# AUPSC.net
KiCad netlist of a schematic drawn in Altium Designer
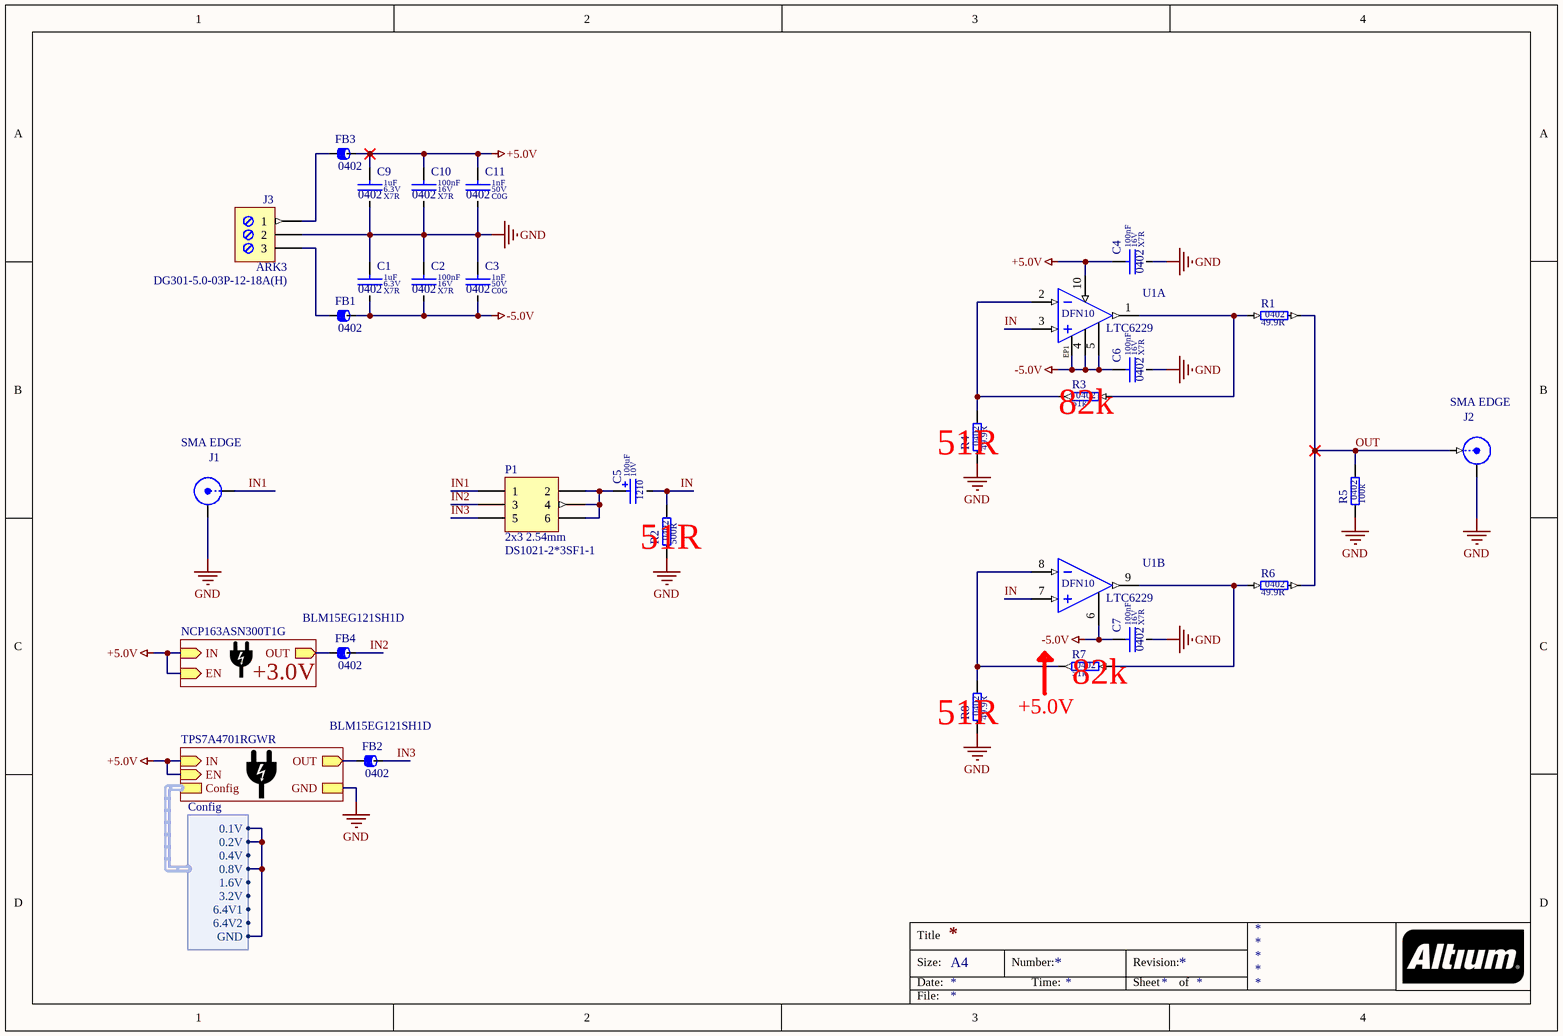
[diagram p0: AUPSC.SchDoc]

(export (version "E")
  (design (tool "Eeschema 10.0.6"))
  (components
    (comp (ref "C1")
      (value "1uF")
      (footprint "C_0402_1005")
      (description "Capacitor")
      (fields
        (field (name "DIELECTRIC") "X7R")
        (field (name "VOLTAGE") "6.3V")
        (field (name "SCH_FOOTPRINT") "0402")
        (field (name "PART NUMBER") "C_1uF_6.3V_X7R_0402_10")
        (field (name "MANUFACTURER") "Murata")
      )
      (libsource (lib "Library") (part "C"))
    )
    (comp (ref "C2")
      (value "100nF")
      (footprint "C_0402_1005")
      (description "Capacitor")
      (fields
        (field (name "DIELECTRIC") "X7R")
        (field (name "VOLTAGE") "16V")
        (field (name "SCH_FOOTPRINT") "0402")
        (field (name "PART NUMBER") "C_100nF_16V_X7R_0402_10")
        (field (name "MANUFACTURER") "Murata")
      )
      (libsource (lib "Library") (part "C"))
    )
    (comp (ref "C3")
      (value "1nF")
      (footprint "C_0402_1005")
      (description "Capacitor")
      (fields
        (field (name "DIELECTRIC") "C0G")
        (field (name "VOLTAGE") "50V")
        (field (name "SCH_FOOTPRINT") "0402")
        (field (name "PART NUMBER") "C_1nF_50V_C0G_0402_5")
        (field (name "MANUFACTURER") "Murata")
      )
      (libsource (lib "Library") (part "C"))
    )
    (comp (ref "C4")
      (value "100nF")
      (footprint "C_0402_1005")
      (description "Capacitor")
      (fields
        (field (name "DIELECTRIC") "X7R")
        (field (name "VOLTAGE") "16V")
        (field (name "SCH_FOOTPRINT") "0402")
        (field (name "PART NUMBER") "C_100nF_16V_X7R_0402_10")
        (field (name "MANUFACTURER") "Murata")
      )
      (libsource (lib "Library") (part "C"))
    )
    (comp (ref "C5")
      (value "100uF")
      (footprint "CT_1210_3225")
      (description "Capacitor")
      (fields
        (field (name "SCH_FOOTPRINT") "1210")
        (field (name "VOLTAGE") "10V")
        (field (name "PART NUMBER") "CT_100uF_10V_TA2O5_1210_20")
        (field (name "MANUFACTURER") "AVX")
      )
      (libsource (lib "Library") (part "CT"))
    )
    (comp (ref "C6")
      (value "100nF")
      (footprint "C_0402_1005")
      (description "Capacitor")
      (fields
        (field (name "DIELECTRIC") "X7R")
        (field (name "VOLTAGE") "16V")
        (field (name "SCH_FOOTPRINT") "0402")
        (field (name "PART NUMBER") "C_100nF_16V_X7R_0402_10")
        (field (name "MANUFACTURER") "Murata")
      )
      (libsource (lib "Library") (part "C"))
    )
    (comp (ref "C7")
      (value "100nF")
      (footprint "C_0402_1005")
      (description "Capacitor")
      (fields
        (field (name "DIELECTRIC") "X7R")
        (field (name "VOLTAGE") "16V")
        (field (name "SCH_FOOTPRINT") "0402")
        (field (name "PART NUMBER") "C_100nF_16V_X7R_0402_10")
        (field (name "MANUFACTURER") "Murata")
      )
      (libsource (lib "Library") (part "C"))
    )
    (comp (ref "C9")
      (value "1uF")
      (footprint "C_0402_1005")
      (description "Capacitor")
      (fields
        (field (name "DIELECTRIC") "X7R")
        (field (name "VOLTAGE") "6.3V")
        (field (name "SCH_FOOTPRINT") "0402")
        (field (name "PART NUMBER") "C_1uF_6.3V_X7R_0402_10")
        (field (name "MANUFACTURER") "Murata")
      )
      (libsource (lib "Library") (part "C"))
    )
    (comp (ref "C10")
      (value "100nF")
      (footprint "C_0402_1005")
      (description "Capacitor")
      (fields
        (field (name "DIELECTRIC") "X7R")
        (field (name "VOLTAGE") "16V")
        (field (name "SCH_FOOTPRINT") "0402")
        (field (name "PART NUMBER") "C_100nF_16V_X7R_0402_10")
        (field (name "MANUFACTURER") "Murata")
      )
      (libsource (lib "Library") (part "C"))
    )
    (comp (ref "C11")
      (value "1nF")
      (footprint "C_0402_1005")
      (description "Capacitor")
      (fields
        (field (name "DIELECTRIC") "C0G")
        (field (name "VOLTAGE") "50V")
        (field (name "SCH_FOOTPRINT") "0402")
        (field (name "PART NUMBER") "C_1nF_50V_C0G_0402_5")
        (field (name "MANUFACTURER") "Murata")
      )
      (libsource (lib "Library") (part "C"))
    )
    (comp (ref "FB1")
      (value "Ferrite bead")
      (footprint "FB_0402_1005")
      (description "Ferrite Bead")
      (fields
        (field (name "PART NUMBER") "FB_BLM15EG121SH1D")
        (field (name "SCH_FOOTPRINT") "0402")
        (field (name "MANUFACTURER") "Murata")
      )
      (libsource (lib "Library") (part "FB"))
    )
    (comp (ref "FB2")
      (value "BLM15EG121SH1D")
      (footprint "FB_0402_1005")
      (description "Ferrite Bead")
      (fields
        (field (name "PART NUMBER") "FB_BLM15EG121SH1D")
        (field (name "SCH_FOOTPRINT") "0402")
        (field (name "MANUFACTURER") "Murata")
      )
      (libsource (lib "Library") (part "FB"))
    )
    (comp (ref "FB3")
      (value "Ferrite bead")
      (footprint "FB_0402_1005")
      (description "Ferrite Bead")
      (fields
        (field (name "PART NUMBER") "FB_BLM15EG121SH1D")
        (field (name "SCH_FOOTPRINT") "0402")
        (field (name "MANUFACTURER") "Murata")
      )
      (libsource (lib "") (part "FB_1"))
    )
    (comp (ref "FB4")
      (value "BLM15EG121SH1D")
      (footprint "FB_0402_1005")
      (description "Ferrite Bead")
      (fields
        (field (name "PART NUMBER") "FB_BLM15EG121SH1D")
        (field (name "SCH_FOOTPRINT") "0402")
        (field (name "MANUFACTURER") "Murata")
      )
      (libsource (lib "Library") (part "FB"))
    )
    (comp (ref "J1")
      (value "SMA EDGE")
      (footprint "J_SMA_EDGE")
      (description "SMA connector")
      (fields (field (name "PART NUMBER") "J_SMA_EDGE_UNIVERSAL") (field (name "SCH_FOOTPRINT") "SMA EDGE"))
      (libsource (lib "Library") (part "J_SMA"))
    )
    (comp (ref "J2")
      (value "SMA EDGE")
      (footprint "J_SMA_EDGE")
      (description "SMA connector")
      (fields (field (name "PART NUMBER") "J_SMA_EDGE_UNIVERSAL") (field (name "SCH_FOOTPRINT") "SMA EDGE"))
      (libsource (lib "") (part "J_SMA_1"))
    )
    (comp (ref "J3")
      (value "DG301-5.0-03P-12-18A(H)")
      (footprint "J_ARK3")
      (description "ARK Screw terminal, 3-Pin")
      (fields
        (field (name "SCH_FOOTPRINT") "ARK3")
        (field (name "PART NUMBER") "J_TB-5.0-P-3P")
        (field (name "MANUFACTURER") "DEGSON ELECTRONICS")
      )
      (libsource (lib "Library") (part "J_ARK3"))
    )
    (comp (ref "P1")
      (value "DS1021-2*3SF1-1")
      (footprint "P_HEADER_2x3_2.54")
      (description "Pin Header")
      (fields
        (field (name "SCH_FOOTPRINT") "2x3 2.54mm")
        (field (name "PART NUMBER") "P_HEADER_2x3_2.54")
        (field (name "MANUFACTURER") "Connfly")
      )
      (libsource (lib "Library") (part "P_HEADER_2x3"))
    )
    (comp (ref "R1")
      (value "49.9R")
      (footprint "R_0402_1005")
      (fields
        (field (name "SCH_FOOTPRINT") "0402")
        (field (name "PART NUMBER") "R_49.9R_0402_1")
        (field (name "VOLTAGE") "50V")
        (field (name "POWER") "100mW")
      )
      (libsource (lib "") (part "R_2"))
    )
    (comp (ref "R2")
      (value "500R")
      (footprint "R_0402_1005")
      (fields
        (field (name "SCH_FOOTPRINT") "0402")
        (field (name "PART NUMBER") "R_500R_0402_0.1")
        (field (name "VOLTAGE") "75V")
        (field (name "POWER") "50mW")
      )
      (libsource (lib "Library") (part "R"))
    )
    (comp (ref "R3")
      (value "51k")
      (footprint "R_0402_1005")
      (fields
        (field (name "SCH_FOOTPRINT") "0402")
        (field (name "PART NUMBER") "R_51k_0402_1")
        (field (name "VOLTAGE") "50V")
        (field (name "POWER") "62.5mW")
      )
      (libsource (lib "") (part "R_1"))
    )
    (comp (ref "R4")
      (value "49.9R")
      (footprint "R_0402_1005")
      (fields
        (field (name "SCH_FOOTPRINT") "0402")
        (field (name "PART NUMBER") "R_49.9R_0402_1")
        (field (name "VOLTAGE") "50V")
        (field (name "POWER") "100mW")
      )
      (libsource (lib "Library") (part "R"))
    )
    (comp (ref "R5")
      (value "100k")
      (footprint "R_0402_1005")
      (fields
        (field (name "SCH_FOOTPRINT") "0402")
        (field (name "PART NUMBER") "R_100k_0402_1")
        (field (name "VOLTAGE") "50V")
        (field (name "POWER") "63mW")
      )
      (libsource (lib "Library") (part "R"))
    )
    (comp (ref "R6")
      (value "49.9R")
      (footprint "R_0402_1005")
      (fields
        (field (name "SCH_FOOTPRINT") "0402")
        (field (name "PART NUMBER") "R_49.9R_0402_1")
        (field (name "VOLTAGE") "50V")
        (field (name "POWER") "100mW")
      )
      (libsource (lib "") (part "R_2"))
    )
    (comp (ref "R7")
      (value "51k")
      (footprint "R_0402_1005")
      (fields
        (field (name "SCH_FOOTPRINT") "0402")
        (field (name "PART NUMBER") "R_51k_0402_1")
        (field (name "VOLTAGE") "50V")
        (field (name "POWER") "62.5mW")
      )
      (libsource (lib "") (part "R_1"))
    )
    (comp (ref "R8")
      (value "49.9R")
      (footprint "R_0402_1005")
      (fields
        (field (name "SCH_FOOTPRINT") "0402")
        (field (name "PART NUMBER") "R_49.9R_0402_1")
        (field (name "VOLTAGE") "50V")
        (field (name "POWER") "100mW")
      )
      (libsource (lib "Library") (part "R"))
    )
    (comp (ref "U1")
      (value "LTC6229")
      (footprint "DFN10_3x3_EP")
      (fields
        (field (name "SCH_FOOTPRINT") "DFN10")
        (field (name "PART NUMBER") "U_ADA4807-2ACPZ-R2")
        (field (name "MANUFACTURER") "Analog Devices")
        (field (name "MANUFACTURER PART NUMBER") "ADA4807-2ACPZ-R2")
      )
      (libsource (lib "Library") (part "A_10PIN_TYPICAL"))
    )
  )
  (nets
    (net (code "2") (name "+5.0V") (class "Default")
      (node (ref "C10") (pin "1") (pinfunction "1_1") (pintype "passive"))
      (node (ref "C11") (pin "1") (pinfunction "1_1") (pintype "passive"))
      (node (ref "C4") (pin "1") (pinfunction "1_1") (pintype "passive"))
      (node (ref "C9") (pin "1") (pinfunction "1_1") (pintype "passive"))
      (node (ref "FB3") (pin "2") (pintype "output"))
      (node (ref "U1") (pin "10") (pinfunction "VDD_10") (pintype "input"))
    )
    (net (code "3") (name "-5.0V") (class "Default")
      (node (ref "C1") (pin "2") (pinfunction "2_2") (pintype "passive"))
      (node (ref "C2") (pin "2") (pinfunction "2_2") (pintype "passive"))
      (node (ref "C3") (pin "2") (pinfunction "2_2") (pintype "passive"))
      (node (ref "C6") (pin "1") (pinfunction "1_1") (pintype "passive"))
      (node (ref "C7") (pin "1") (pinfunction "1_1") (pintype "passive"))
      (node (ref "FB1") (pin "2") (pintype "passive"))
      (node (ref "U1") (pin "4") (pinfunction "GND_4") (pintype "power_in"))
      (node (ref "U1") (pin "5") (pinfunction "~{SHNDA}_5") (pintype "power_in"))
      (node (ref "U1") (pin "6") (pinfunction "~{SHNDB}_6") (pintype "power_in"))
      (node (ref "U1") (pin "EP1") (pinfunction "GND_EP1") (pintype "power_in"))
    )
    (net (code "4") (name "/IN") (class "Default")
      (node (ref "C5") (pin "2") (pinfunction "2_2") (pintype "passive"))
      (node (ref "R2") (pin "2") (pinfunction "2_2") (pintype "passive"))
      (node (ref "U1") (pin "3") (pinfunction "IN+_3") (pintype "input"))
      (node (ref "U1") (pin "7") (pinfunction "IN+_7") (pintype "input"))
    )
    (net (code "5") (name "/IN1") (class "Default")
      (node (ref "J1") (pin "1") (pinfunction "X_1") (pintype "passive"))
      (node (ref "P1") (pin "1") (pinfunction "1_1") (pintype "passive"))
    )
    (net (code "6") (name "/IN2") (class "Default")
      (node (ref "FB4") (pin "2") (pintype "passive"))
      (node (ref "P1") (pin "3") (pinfunction "3_3") (pintype "passive"))
    )
    (net (code "7") (name "/IN3") (class "Default")
      (node (ref "FB2") (pin "2") (pintype "passive"))
      (node (ref "P1") (pin "5") (pinfunction "5_5") (pintype "passive"))
    )
    (net (code "8") (name "/OUT") (class "Default")
      (node (ref "J2") (pin "1") (pinfunction "X_1") (pintype "input"))
      (node (ref "R1") (pin "2") (pinfunction "2_2") (pintype "output"))
      (node (ref "R5") (pin "2") (pinfunction "2_2") (pintype "passive"))
      (node (ref "R6") (pin "2") (pinfunction "2_2") (pintype "output"))
    )
    (net (code "9") (name "/OUT_1") (class "Default") (node (ref "FB2") (pin "1") (pintype "passive")))
    (net (code "10") (name "/OUT_2") (class "Default") (node (ref "FB4") (pin "1") (pintype "passive")))
    (net (code "12") (name "GND") (class "Default")
      (node (ref "C1") (pin "1") (pinfunction "1_1") (pintype "passive"))
      (node (ref "C10") (pin "2") (pinfunction "2_2") (pintype "passive"))
      (node (ref "C11") (pin "2") (pinfunction "2_2") (pintype "passive"))
      (node (ref "C2") (pin "1") (pinfunction "1_1") (pintype "passive"))
      (node (ref "C3") (pin "1") (pinfunction "1_1") (pintype "passive"))
      (node (ref "C4") (pin "2") (pinfunction "2_2") (pintype "passive"))
      (node (ref "C6") (pin "2") (pinfunction "2_2") (pintype "passive"))
      (node (ref "C7") (pin "2") (pinfunction "2_2") (pintype "passive"))
      (node (ref "C9") (pin "2") (pinfunction "2_2") (pintype "passive"))
      (node (ref "J1") (pin "2") (pinfunction "GND_2") (pintype "power_in"))
      (node (ref "J2") (pin "2") (pinfunction "GND_2") (pintype "power_in"))
      (node (ref "J3") (pin "2") (pinfunction "2_2") (pintype "passive"))
      (node (ref "R2") (pin "1") (pinfunction "1_1") (pintype "passive"))
      (node (ref "R4") (pin "1") (pinfunction "1_1") (pintype "passive"))
      (node (ref "R5") (pin "1") (pinfunction "1_1") (pintype "passive"))
      (node (ref "R8") (pin "1") (pinfunction "1_1") (pintype "passive"))
    )
    (net (code "13") (name "Net-(C5-Pad1)") (class "Default")
      (node (ref "C5") (pin "1") (pinfunction "1_1") (pintype "passive"))
      (node (ref "P1") (pin "2") (pinfunction "2_2") (pintype "passive"))
      (node (ref "P1") (pin "4") (pinfunction "4_4") (pintype "output"))
      (node (ref "P1") (pin "6") (pinfunction "6_6") (pintype "passive"))
    )
    (net (code "14") (name "Net-(FB1-Pad1)") (class "Default")
      (node (ref "FB1") (pin "1") (pintype "passive"))
      (node (ref "J3") (pin "3") (pinfunction "3_3") (pintype "passive"))
    )
    (net (code "15") (name "Net-(FB3-Pad1)") (class "Default")
      (node (ref "FB3") (pin "1") (pintype "input"))
      (node (ref "J3") (pin "1") (pinfunction "1_1") (pintype "output"))
    )
    (net (code "16") (name "Net-(U1A-IN-)") (class "Default")
      (node (ref "R3") (pin "1") (pinfunction "1_1") (pintype "output"))
      (node (ref "R4") (pin "2") (pinfunction "2_2") (pintype "passive"))
      (node (ref "U1") (pin "2") (pinfunction "IN-_2") (pintype "input"))
    )
    (net (code "17") (name "Net-(U1A-OUT)") (class "Default")
      (node (ref "R1") (pin "1") (pinfunction "1_1") (pintype "input"))
      (node (ref "R3") (pin "2") (pinfunction "2_2") (pintype "input"))
      (node (ref "U1") (pin "1") (pinfunction "OUT_1") (pintype "output"))
    )
    (net (code "18") (name "Net-(U1B-IN-)") (class "Default")
      (node (ref "R7") (pin "1") (pinfunction "1_1") (pintype "output"))
      (node (ref "R8") (pin "2") (pinfunction "2_2") (pintype "passive"))
      (node (ref "U1") (pin "8") (pinfunction "IN-_8") (pintype "input"))
    )
    (net (code "19") (name "Net-(U1B-OUT)") (class "Default")
      (node (ref "R6") (pin "1") (pinfunction "1_1") (pintype "input"))
      (node (ref "R7") (pin "2") (pinfunction "2_2") (pintype "input"))
      (node (ref "U1") (pin "9") (pinfunction "OUT_9") (pintype "output"))
    )
  )
)
